# Microcontroller.net
KiCad netlist of a schematic drawn in Altium Designer
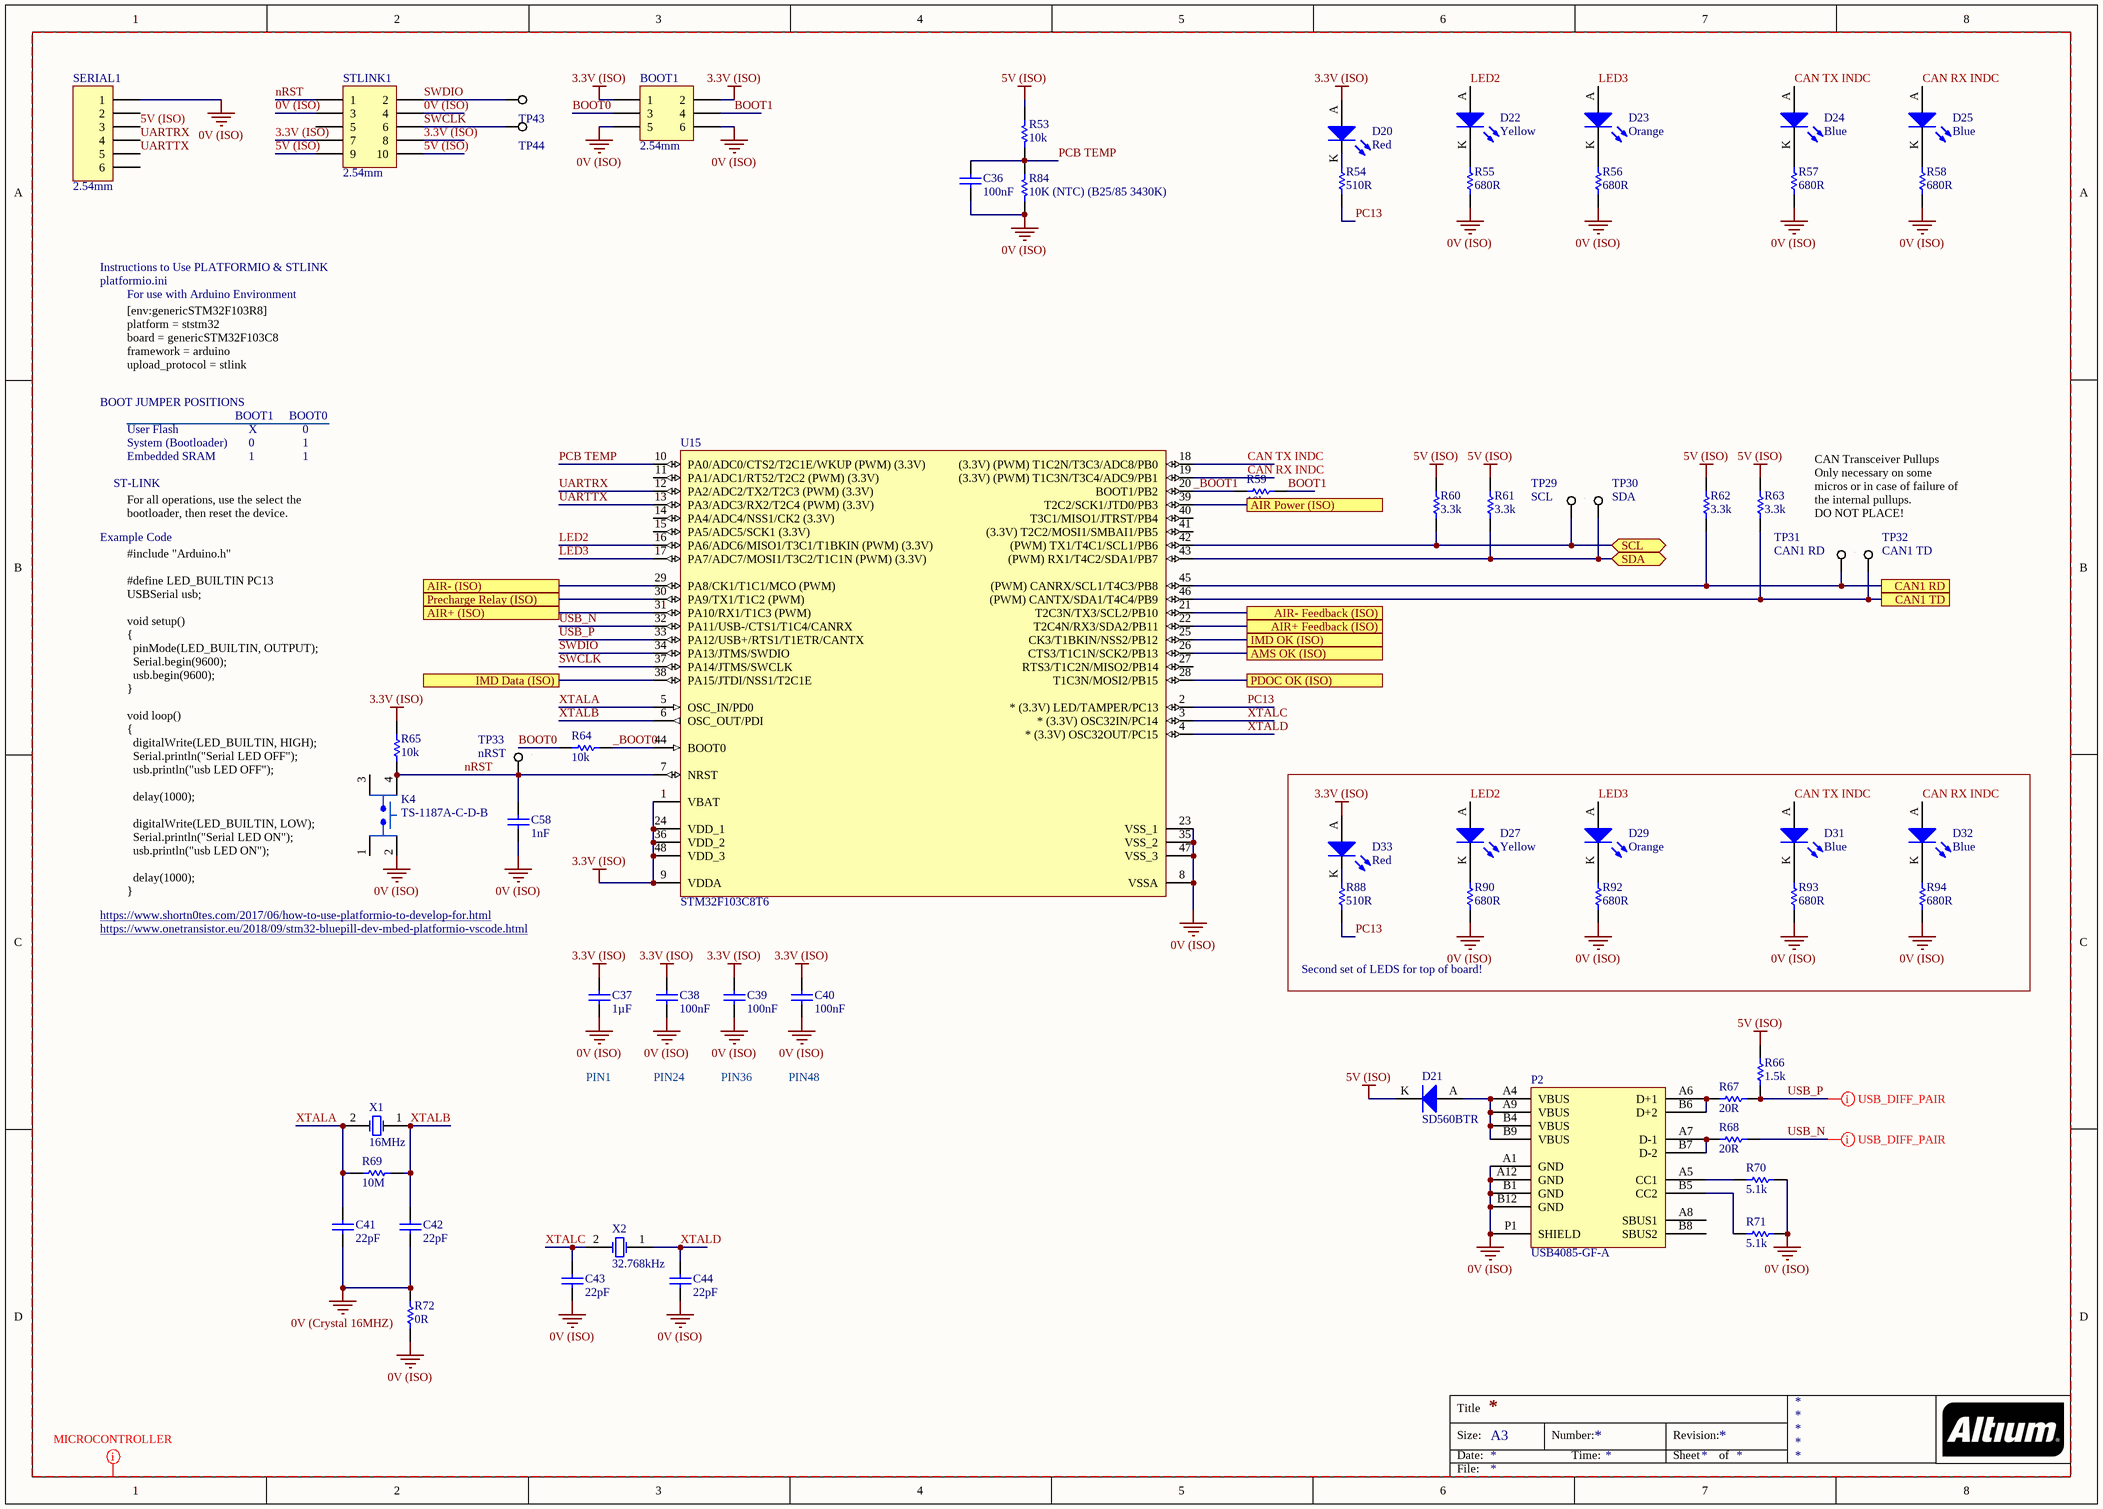
[diagram p0: Microcontroller.SchDoc]

(export (version "E")
  (design (tool "Eeschema 10.0.6"))
  (components
    (comp (ref "BOOT1")
      (value "2.54mm")
      (footprint "TH 2.54mm Header 2x3")
      (fields (field (name "PART NUMBER") "TH 2.54mm Header 2x3") (field (name "CONTACT") "NA"))
      (libsource (lib "ts_20-standard-connectors") (part "Header 2x3"))
    )
    (comp (ref "C36")
      (value "100nF")
      (footprint "0805")
      (fields
        (field (name "PART NUMBER") "GCM21BR71E104KA37L")
        (field (name "TOLERANCE") "10%")
        (field (name "MANUFACTURER") "muRata")
      )
      (libsource (lib "ts_20-standard-library") (part "Capacitor"))
    )
    (comp (ref "C37")
      (value "1µF")
      (footprint "0805")
      (fields
        (field (name "PART NUMBER") "GCM21BR71H105KA03L")
        (field (name "TOLERANCE") "±10%")
        (field (name "MANUFACTURER") "muRata")
      )
      (libsource (lib "ts_20-standard-library") (part "Capacitor"))
    )
    (comp (ref "C38")
      (value "100nF")
      (footprint "0805")
      (fields
        (field (name "PART NUMBER") "GCM21BR71H104KA37L")
        (field (name "TOLERANCE") "±10%")
        (field (name "MANUFACTURER") "muRata")
      )
      (libsource (lib "ts_20-standard-library") (part "Capacitor"))
    )
    (comp (ref "C39")
      (value "100nF")
      (footprint "0805")
      (fields
        (field (name "PART NUMBER") "GCM21BR71H104KA37L")
        (field (name "TOLERANCE") "±10%")
        (field (name "MANUFACTURER") "muRata")
      )
      (libsource (lib "ts_20-standard-library") (part "Capacitor"))
    )
    (comp (ref "C40")
      (value "100nF")
      (footprint "0805")
      (fields
        (field (name "PART NUMBER") "GCM21BR71H104KA37L")
        (field (name "TOLERANCE") "±10%")
        (field (name "MANUFACTURER") "muRata")
      )
      (libsource (lib "ts_20-standard-library") (part "Capacitor"))
    )
    (comp (ref "C41")
      (value "22pF")
      (footprint "0805")
      (fields
        (field (name "PART NUMBER") "GRM21A5C2E220JW01D")
        (field (name "TOLERANCE") "±5%")
        (field (name "MANUFACTURER") "muRata")
      )
      (libsource (lib "ts_20-standard-library") (part "Capacitor"))
    )
    (comp (ref "C42")
      (value "22pF")
      (footprint "0805")
      (fields
        (field (name "PART NUMBER") "GRM21A5C2E220JW01D")
        (field (name "TOLERANCE") "±5%")
        (field (name "MANUFACTURER") "muRata")
      )
      (libsource (lib "ts_20-standard-library") (part "Capacitor"))
    )
    (comp (ref "C43")
      (value "22pF")
      (footprint "0805")
      (fields
        (field (name "PART NUMBER") "GRM21A5C2E220JW01D")
        (field (name "TOLERANCE") "±5%")
        (field (name "MANUFACTURER") "muRata")
      )
      (libsource (lib "ts_20-standard-library") (part "Capacitor"))
    )
    (comp (ref "C44")
      (value "22pF")
      (footprint "0805")
      (fields
        (field (name "PART NUMBER") "GRM21A5C2E220JW01D")
        (field (name "TOLERANCE") "±5%")
        (field (name "MANUFACTURER") "muRata")
      )
      (libsource (lib "ts_20-standard-library") (part "Capacitor"))
    )
    (comp (ref "C58")
      (value "1nF")
      (footprint "0805")
      (fields
        (field (name "PART NUMBER") "GCM21BR71H102KA37L")
        (field (name "TOLERANCE") "10%")
        (field (name "MANUFACTURER") "muRata")
      )
      (libsource (lib "ts_20-standard-library") (part "Capacitor"))
    )
    (comp (ref "D20")
      (value "Red")
      (footprint "0805 LED")
      (description "Red LED Indication - Discrete 1.75V 0805 (2012 Metric)")
      (fields (field (name "MANUFACTURER") "ROHM Semiconductor") (field (name "PART NUMBER") "SML-210LTT86"))
      (libsource (lib "ts_20-standard-library") (part "LED"))
    )
    (comp (ref "D21")
      (value "SD560BTR")
      (footprint "SMB Diode")
      (description "1.2V_F 600V 5A SMB")
      (fields
        (field (name "MANUFACTURER") "SMC Diode Solutions")
        (field (name "DIGIKEY PART NUMBER") "1655-1530-2-ND")
      )
      (libsource (lib "ts_20-standard-library") (part "Diode"))
    )
    (comp (ref "D22")
      (value "Yellow")
      (footprint "0805 LED")
      (description "Yellow LED Indication - Discrete 1.75V 0805 (2012 Metric)")
      (fields (field (name "PART NUMBER") "SML-211YTT86") (field (name "MANUFACTURER") "ROHM Semiconductor"))
      (libsource (lib "ts_20-standard-library") (part "LED"))
    )
    (comp (ref "D23")
      (value "Orange")
      (footprint "0805 LED")
      (description "Orange LED Indication - Discrete 1.75V 0805 (2012 Metric)")
      (fields (field (name "PART NUMBER") "SML-211DTT86") (field (name "MANUFACTURER") "ROHM Semiconductor"))
      (libsource (lib "ts_20-standard-library") (part "LED"))
    )
    (comp (ref "D24")
      (value "Blue")
      (footprint "0805 LED")
      (description "LED BLUE CLEAR 2012 SMD")
      (fields
        (field (name "PART NUMBER") "SML-MN2BCTT86C")
        (field (name "MANUFACTURER") "ROHM Semiconductor")
      )
      (libsource (lib "ts_20-standard-library") (part "LED"))
    )
    (comp (ref "D25")
      (value "Blue")
      (footprint "0805 LED")
      (description "LED BLUE CLEAR 2012 SMD")
      (fields
        (field (name "PART NUMBER") "SML-MN2BCTT86C")
        (field (name "MANUFACTURER") "ROHM Semiconductor")
      )
      (libsource (lib "ts_20-standard-library") (part "LED"))
    )
    (comp (ref "D27")
      (value "Yellow")
      (footprint "0805 LED")
      (description "Yellow LED Indication - Discrete 1.75V 0805 (2012 Metric)")
      (fields (field (name "PART NUMBER") "SML-211YTT86") (field (name "MANUFACTURER") "ROHM Semiconductor"))
      (libsource (lib "ts_20-standard-library") (part "LED"))
    )
    (comp (ref "D29")
      (value "Orange")
      (footprint "0805 LED")
      (description "Orange LED Indication - Discrete 1.75V 0805 (2012 Metric)")
      (fields (field (name "PART NUMBER") "SML-211DTT86") (field (name "MANUFACTURER") "ROHM Semiconductor"))
      (libsource (lib "ts_20-standard-library") (part "LED"))
    )
    (comp (ref "D31")
      (value "Blue")
      (footprint "0805 LED")
      (description "LED BLUE CLEAR 2012 SMD")
      (fields
        (field (name "PART NUMBER") "SML-MN2BCTT86C")
        (field (name "MANUFACTURER") "ROHM Semiconductor")
      )
      (libsource (lib "ts_20-standard-library") (part "LED"))
    )
    (comp (ref "D32")
      (value "Blue")
      (footprint "0805 LED")
      (description "LED BLUE CLEAR 2012 SMD")
      (fields
        (field (name "PART NUMBER") "SML-MN2BCTT86C")
        (field (name "MANUFACTURER") "ROHM Semiconductor")
      )
      (libsource (lib "ts_20-standard-library") (part "LED"))
    )
    (comp (ref "D33")
      (value "Red")
      (footprint "0805 LED")
      (description "Red LED Indication - Discrete 1.75V 0805 (2012 Metric)")
      (fields (field (name "MANUFACTURER") "ROHM Semiconductor") (field (name "PART NUMBER") "SML-210LTT86"))
      (libsource (lib "ts_20-standard-library") (part "LED"))
    )
    (comp (ref "K4")
      (value "TS-1187A-C-D-B")
      (footprint "XKB SW-4.5")
      (description "TACTILE SWITCHES SPST 5.10MM X 5.10MM 0.80MM SMD ROHS")
      (fields (field (name "MANUFACTURER") "XKB Enerprise"))
      (libsource (lib "ts_20-standard-library") (part "SPST (Mom) Push Button"))
    )
    (comp (ref "P2")
      (value "USB4085-GF-A")
      (footprint "USB4085-GF-A")
      (description "USB - C (Type - C) USB 2.0 Receptacle Connector 16 Position Through Hole, Right Angle")
      (fields (field (name "DIGIKEY PART NUMBER") "2073-USB4085-GF-ACT-ND"))
      (libsource (lib "ts_20-standard-connectors") (part "USB4085-GF-A"))
    )
    (comp (ref "R53")
      (value "10k")
      (footprint "0805")
      (fields
        (field (name "PART NUMBER") "RC0805FR0710KL")
        (field (name "MANUFACTURER") "YAGEO")
        (field (name "TOLERANCE") "0.01")
      )
      (libsource (lib "ts_20-standard-library") (part "Resistor"))
    )
    (comp (ref "R54")
      (value "510R")
      (footprint "0805")
      (fields
        (field (name "MANUFACTURER") "YAGEO")
        (field (name "PART NUMBER") "RC0805FR07510RL")
        (field (name "TOLERANCE") "0.01")
      )
      (libsource (lib "ts_20-standard-library") (part "Resistor"))
    )
    (comp (ref "R55")
      (value "680R")
      (footprint "0805")
      (fields
        (field (name "PART NUMBER") "RC0805FR07680RL")
        (field (name "MANUFACTURER") "YAGEO")
        (field (name "TOLERANCE") "0.01")
      )
      (libsource (lib "ts_20-standard-library") (part "Resistor"))
    )
    (comp (ref "R56")
      (value "680R")
      (footprint "0805")
      (fields
        (field (name "PART NUMBER") "RC0805FR07680RL")
        (field (name "MANUFACTURER") "YAGEO")
        (field (name "TOLERANCE") "0.01")
      )
      (libsource (lib "ts_20-standard-library") (part "Resistor"))
    )
    (comp (ref "R57")
      (value "680R")
      (footprint "0805")
      (fields
        (field (name "PART NUMBER") "RC0805FR07680RL")
        (field (name "MANUFACTURER") "YAGEO")
        (field (name "TOLERANCE") "0.01")
      )
      (libsource (lib "ts_20-standard-library") (part "Resistor"))
    )
    (comp (ref "R58")
      (value "680R")
      (footprint "0805")
      (fields
        (field (name "PART NUMBER") "RC0805FR07680RL")
        (field (name "MANUFACTURER") "YAGEO")
        (field (name "TOLERANCE") "0.01")
      )
      (libsource (lib "ts_20-standard-library") (part "Resistor"))
    )
    (comp (ref "R59")
      (value "10k")
      (footprint "0805")
      (fields
        (field (name "PART NUMBER") "RC0805FR0710KL")
        (field (name "MANUFACTURER") "YAGEO")
        (field (name "TOLERANCE") "0.01")
      )
      (libsource (lib "ts_20-standard-library") (part "Resistor"))
    )
    (comp (ref "R60")
      (value "3.3k")
      (footprint "0805")
      (fields
        (field (name "PART NUMBER") "RC0805FR073K3L")
        (field (name "MANUFACTURER") "YAGEO")
        (field (name "TOLERANCE") "0.01")
      )
      (libsource (lib "ts_20-standard-library") (part "Resistor"))
    )
    (comp (ref "R61")
      (value "3.3k")
      (footprint "0805")
      (fields
        (field (name "PART NUMBER") "RC0805FR073K3L")
        (field (name "MANUFACTURER") "YAGEO")
        (field (name "TOLERANCE") "0.01")
      )
      (libsource (lib "ts_20-standard-library") (part "Resistor"))
    )
    (comp (ref "R62")
      (value "3.3k")
      (footprint "0805")
      (fields
        (field (name "PART NUMBER") "RC0805FR073K3L")
        (field (name "MANUFACTURER") "YAGEO")
        (field (name "TOLERANCE") "0.01")
      )
      (libsource (lib "ts_20-standard-library") (part "Resistor"))
    )
    (comp (ref "R63")
      (value "3.3k")
      (footprint "0805")
      (fields
        (field (name "PART NUMBER") "RC0805FR073K3L")
        (field (name "MANUFACTURER") "YAGEO")
        (field (name "TOLERANCE") "0.01")
      )
      (libsource (lib "ts_20-standard-library") (part "Resistor"))
    )
    (comp (ref "R64")
      (value "10k")
      (footprint "0805")
      (fields
        (field (name "PART NUMBER") "RC0805FR0710KL")
        (field (name "MANUFACTURER") "YAGEO")
        (field (name "TOLERANCE") "0.01")
      )
      (libsource (lib "ts_20-standard-library") (part "Resistor"))
    )
    (comp (ref "R65")
      (value "10k")
      (footprint "0805")
      (fields
        (field (name "MANUFACTURER") "YAGEO")
        (field (name "PART NUMBER") "RC0805FR0710KL")
        (field (name "TOLERANCE") "0.01")
      )
      (libsource (lib "ts_20-standard-library") (part "Resistor"))
    )
    (comp (ref "R66")
      (value "1.5k")
      (footprint "0805")
      (fields
        (field (name "PART NUMBER") "RC0805FR071K5L")
        (field (name "MANUFACTURER") "YAGEO")
        (field (name "TOLERANCE") "0.01")
      )
      (libsource (lib "ts_20-standard-library") (part "Resistor"))
    )
    (comp (ref "R67")
      (value "20R")
      (footprint "0805")
      (fields
        (field (name "PART NUMBER") "RC0805FR0720RL")
        (field (name "MANUFACTURER") "YAGEO")
        (field (name "TOLERANCE") "0.01")
      )
      (libsource (lib "ts_20-standard-library") (part "Resistor"))
    )
    (comp (ref "R68")
      (value "20R")
      (footprint "0805")
      (fields
        (field (name "PART NUMBER") "RC0805FR0720RL")
        (field (name "MANUFACTURER") "YAGEO")
        (field (name "TOLERANCE") "0.01")
      )
      (libsource (lib "ts_20-standard-library") (part "Resistor"))
    )
    (comp (ref "R69")
      (value "10M")
      (footprint "0805")
      (fields
        (field (name "PART NUMBER") "RC0805FR0710ML")
        (field (name "MANUFACTURER") "YAGEO")
        (field (name "TOLERANCE") "0.01")
      )
      (libsource (lib "ts_20-standard-library") (part "Resistor"))
    )
    (comp (ref "R70")
      (value "5.1k")
      (footprint "0805")
      (fields
        (field (name "PART NUMBER") "RC0805FR075K1L")
        (field (name "MANUFACTURER") "YAGEO")
        (field (name "TOLERANCE") "0.01")
      )
      (libsource (lib "ts_20-standard-library") (part "Resistor"))
    )
    (comp (ref "R71")
      (value "5.1k")
      (footprint "0805")
      (fields
        (field (name "PART NUMBER") "RC0805FR075K1L")
        (field (name "MANUFACTURER") "YAGEO")
        (field (name "TOLERANCE") "0.01")
      )
      (libsource (lib "ts_20-standard-library") (part "Resistor"))
    )
    (comp (ref "R72")
      (value "0R")
      (footprint "0805")
      (fields
        (field (name "PART NUMBER") "RC0805FR070RL")
        (field (name "MANUFACTURER") "YAGEO")
        (field (name "TOLERANCE") "0.01")
      )
      (libsource (lib "ts_20-standard-library") (part "Resistor"))
    )
    (comp (ref "R84")
      (value "10K (NTC) (B25/85 3430K)")
      (footprint "0805")
      (fields
        (field (name "PART NUMBER") "NTCS0805E3103FLT")
        (field (name "MANUFACTURER") "Vishay Beyschlag")
        (field (name "TOLERANCE") "0.01")
      )
      (libsource (lib "ts_20-standard-library") (part "Resistor"))
    )
    (comp (ref "R88")
      (value "510R")
      (footprint "0805")
      (fields
        (field (name "MANUFACTURER") "YAGEO")
        (field (name "PART NUMBER") "RC0805FR07510RL")
        (field (name "TOLERANCE") "0.01")
      )
      (libsource (lib "ts_20-standard-library") (part "Resistor"))
    )
    (comp (ref "R90")
      (value "680R")
      (footprint "0805")
      (fields
        (field (name "PART NUMBER") "RC0805FR07680RL")
        (field (name "MANUFACTURER") "YAGEO")
        (field (name "TOLERANCE") "0.01")
      )
      (libsource (lib "ts_20-standard-library") (part "Resistor"))
    )
    (comp (ref "R92")
      (value "680R")
      (footprint "0805")
      (fields
        (field (name "PART NUMBER") "RC0805FR07680RL")
        (field (name "MANUFACTURER") "YAGEO")
        (field (name "TOLERANCE") "0.01")
      )
      (libsource (lib "ts_20-standard-library") (part "Resistor"))
    )
    (comp (ref "R93")
      (value "680R")
      (footprint "0805")
      (fields
        (field (name "PART NUMBER") "RC0805FR07680RL")
        (field (name "MANUFACTURER") "YAGEO")
        (field (name "TOLERANCE") "0.01")
      )
      (libsource (lib "ts_20-standard-library") (part "Resistor"))
    )
    (comp (ref "R94")
      (value "680R")
      (footprint "0805")
      (fields
        (field (name "PART NUMBER") "RC0805FR07680RL")
        (field (name "MANUFACTURER") "YAGEO")
        (field (name "TOLERANCE") "0.01")
      )
      (libsource (lib "ts_20-standard-library") (part "Resistor"))
    )
    (comp (ref "SERIAL1")
      (value "2.54mm")
      (footprint "TH 2.54mm Header 1x6")
      (fields (field (name "PART NUMBER") "TH 2.54mm Header 1x6") (field (name "CONTACT") "NA"))
      (libsource (lib "ts_20-standard-connectors") (part "Header 1x6"))
    )
    (comp (ref "STLINK1")
      (value "2.54mm")
      (footprint "TH 2.54mm Header 2x5")
      (fields (field (name "PART NUMBER") "TH 2.54mm Header 2x5") (field (name "CONTACT") "NA"))
      (libsource (lib "ts_20-standard-connectors") (part "Header 2x5"))
    )
    (comp (ref "TP29")
      (value "SCL")
      (footprint "SMD Test Point 1mm")
      (fields (field (name "PART NUMBER") "SMD Test Point Small") (field (name "CONTACT") "NA"))
      (libsource (lib "ts_20-standard-connectors") (part "Test Point Small"))
    )
    (comp (ref "TP30")
      (value "SDA")
      (footprint "SMD Test Point 1mm")
      (fields (field (name "PART NUMBER") "SMD Test Point Small") (field (name "CONTACT") "NA"))
      (libsource (lib "ts_20-standard-connectors") (part "Test Point Small"))
    )
    (comp (ref "TP31")
      (value "CAN1 RD")
      (footprint "SMD Test Point 1mm")
      (fields (field (name "PART NUMBER") "SMD Test Point Small") (field (name "CONTACT") "NA"))
      (libsource (lib "ts_20-standard-connectors") (part "Test Point Small"))
    )
    (comp (ref "TP32")
      (value "CAN1 TD")
      (footprint "SMD Test Point 1mm")
      (fields (field (name "PART NUMBER") "SMD Test Point Small") (field (name "CONTACT") "NA"))
      (libsource (lib "ts_20-standard-connectors") (part "Test Point Small"))
    )
    (comp (ref "TP33")
      (value "nRST")
      (footprint "SMD Test Point 1mm")
      (fields (field (name "PART NUMBER") "SMD Test Point Small") (field (name "CONTACT") "NA"))
      (libsource (lib "ts_20-standard-connectors") (part "Test Point Small"))
    )
    (comp (ref "TP43")
      (value "0mm")
      (footprint "SMD Test Point 1mm")
      (fields (field (name "PART NUMBER") "SMD Test Point Small") (field (name "CONTACT") "NA"))
      (libsource (lib "ts_20-standard-connectors") (part "Test Point Small"))
    )
    (comp (ref "TP44")
      (value "0mm")
      (footprint "SMD Test Point 1mm")
      (fields (field (name "PART NUMBER") "SMD Test Point Small") (field (name "CONTACT") "NA"))
      (libsource (lib "ts_20-standard-connectors") (part "Test Point Small"))
    )
    (comp (ref "U15")
      (value "STM32F103C8T6")
      (footprint "STM 48-LQFP")
      (description "ARM® Cortex®-M3 STM32F1 Microcontroller IC 32-Bit 72MHz 64KB (64K x 8) FLASH")
      (fields
        (field (name "MANUFACTURER") "STMicroelectronics")
        (field (name "DIGIKEY PART NUMBER") "497-6063-ND")
      )
      (libsource (lib "ts_20-standard-library") (part "STM32F103C8T6"))
    )
    (comp (ref "X1")
      (value "16MHz")
      (footprint "Abracon HC-49/US")
      (fields
        (field (name "PART NUMBER") "ABLS-16.000MHZ-B4-T")
        (field (name "MANUFACTURER") "Abracon LLC")
        (field (name "DIGIKEY PART NUMBER") "535-10226-1-ND")
      )
      (libsource (lib "ts_20-standard-library") (part "Crystal"))
    )
    (comp (ref "X2")
      (value "32.768kHz")
      (footprint "EPSON 2-SMD")
      (fields
        (field (name "PART NUMBER") "FC-135 32.7680KA-A5")
        (field (name "MANUFACTURER") "EPSON")
        (field (name "DIGIKEY PART NUMBER") "SER4103TR-ND")
      )
      (libsource (lib "ts_20-standard-library") (part "Crystal"))
    )
  )
  (nets
    (net (code "1") (name "/AIR Power (ISO)") (class "Default")
      (node (ref "U15") (pin "39") (pinfunction "T2C2/SCK1/JTD0/PB3_39") (pintype "bidirectional"))
    )
    (net (code "2") (name "/AIR+ (ISO)") (class "Default")
      (node (ref "U15") (pin "31") (pinfunction "PA10/RX1/T1C3_(PWM)_31") (pintype "bidirectional"))
    )
    (net (code "3") (name "/AIR+ Feedback (ISO)") (class "Default")
      (node (ref "U15") (pin "22") (pinfunction "T2C4N/RX3/SDA2/PB11_22") (pintype "bidirectional"))
    )
    (net (code "4") (name "/AIR- (ISO)") (class "Default")
      (node (ref "U15") (pin "29") (pinfunction "PA8/CK1/T1C1/MCO_(PWM)_29") (pintype "bidirectional"))
    )
    (net (code "5") (name "/AIR- Feedback (ISO)") (class "Default")
      (node (ref "U15") (pin "21") (pinfunction "T2C3N/TX3/SCL2/PB10_21") (pintype "bidirectional"))
    )
    (net (code "6") (name "/AMS OK (ISO)") (class "Default")
      (node (ref "U15") (pin "26") (pinfunction "CTS3/T1C1N/SCK2/PB13_26") (pintype "bidirectional"))
    )
    (net (code "7") (name "/BOOT0") (class "Default")
      (node (ref "BOOT1") (pin "3") (pinfunction "3_3") (pintype "passive"))
      (node (ref "R64") (pin "1") (pinfunction "1_1") (pintype "passive"))
    )
    (net (code "8") (name "/BOOT1") (class "Default")
      (node (ref "BOOT1") (pin "4") (pinfunction "4_4") (pintype "passive"))
      (node (ref "R59") (pin "2") (pinfunction "2_2") (pintype "passive"))
    )
    (net (code "9") (name "/CAN RX INDC") (class "Default")
      (node (ref "D25") (pin "A") (pinfunction "A_A") (pintype "passive"))
      (node (ref "D32") (pin "A") (pinfunction "A_A") (pintype "passive"))
      (node (ref "U15") (pin "19") (pinfunction "(3.3V)_(PWM)_T1C3N/T3C4/ADC9/PB1_19") (pintype "bidirectional"))
    )
    (net (code "10") (name "/CAN TX INDC") (class "Default")
      (node (ref "D24") (pin "A") (pinfunction "A_A") (pintype "passive"))
      (node (ref "D31") (pin "A") (pinfunction "A_A") (pintype "passive"))
      (node (ref "U15") (pin "18") (pinfunction "(3.3V)_(PWM)_T1C2N/T3C3/ADC8/PB0_18") (pintype "bidirectional"))
    )
    (net (code "11") (name "/CAN1 RD") (class "Default")
      (node (ref "R62") (pin "1") (pinfunction "1_1") (pintype "passive"))
      (node (ref "TP31") (pin "1") (pinfunction "1_1") (pintype "passive"))
      (node (ref "U15") (pin "45") (pinfunction "(PWM)_CANRX/SCL1/T4C3/PB8_45") (pintype "bidirectional"))
    )
    (net (code "12") (name "/CAN1 TD") (class "Default")
      (node (ref "R63") (pin "1") (pinfunction "1_1") (pintype "passive"))
      (node (ref "TP32") (pin "1") (pinfunction "1_1") (pintype "passive"))
      (node (ref "U15") (pin "46") (pinfunction "(PWM)_CANTX/SDA1/T4C4/PB9_46") (pintype "bidirectional"))
    )
    (net (code "13") (name "/IMD Data (ISO)") (class "Default")
      (node (ref "U15") (pin "38") (pinfunction "PA15/JTDI/NSS1/T2C1E_38") (pintype "bidirectional"))
    )
    (net (code "14") (name "/IMD OK (ISO)") (class "Default")
      (node (ref "U15") (pin "25") (pinfunction "CK3/T1BKIN/NSS2/PB12_25") (pintype "bidirectional"))
    )
    (net (code "15") (name "/LED2") (class "Default")
      (node (ref "D22") (pin "A") (pinfunction "A_A") (pintype "passive"))
      (node (ref "D27") (pin "A") (pinfunction "A_A") (pintype "passive"))
      (node (ref "U15") (pin "16") (pinfunction "PA6/ADC6/MISO1/T3C1/T1BKIN_(PWM)_(3.3V)_16") (pintype "bidirectional"))
    )
    (net (code "16") (name "/LED3") (class "Default")
      (node (ref "D23") (pin "A") (pinfunction "A_A") (pintype "passive"))
      (node (ref "D29") (pin "A") (pinfunction "A_A") (pintype "passive"))
      (node (ref "U15") (pin "17") (pinfunction "PA7/ADC7/MOSI1/T3C2/T1C1N_(PWM)_(3.3V)_17") (pintype "bidirectional"))
    )
    (net (code "17") (name "/PC13") (class "Default")
      (node (ref "R54") (pin "1") (pinfunction "1_1") (pintype "passive"))
      (node (ref "R88") (pin "1") (pinfunction "1_1") (pintype "passive"))
      (node (ref "U15") (pin "2") (pinfunction "*_(3.3V)_LED/TAMPER/PC13_2") (pintype "bidirectional"))
    )
    (net (code "18") (name "/PCB TEMP") (class "Default")
      (node (ref "C36") (pin "2") (pinfunction "2_2") (pintype "passive"))
      (node (ref "R53") (pin "1") (pinfunction "1_1") (pintype "passive"))
      (node (ref "R84") (pin "2") (pinfunction "2_2") (pintype "passive"))
      (node (ref "U15") (pin "10") (pinfunction "PA0/ADC0/CTS2/T2C1E/WKUP_(PWM)_(3.3V)_10") (pintype "bidirectional"))
    )
    (net (code "19") (name "/PDOC OK (ISO)") (class "Default")
      (node (ref "U15") (pin "28") (pinfunction "T1C3N/MOSI2/PB15_28") (pintype "bidirectional"))
    )
    (net (code "20") (name "/Precharge Relay (ISO)") (class "Default")
      (node (ref "U15") (pin "30") (pinfunction "PA9/TX1/T1C2_(PWM)_30") (pintype "bidirectional"))
    )
    (net (code "21") (name "/SCL") (class "Default")
      (node (ref "R60") (pin "1") (pinfunction "1_1") (pintype "passive"))
      (node (ref "TP29") (pin "1") (pinfunction "1_1") (pintype "passive"))
      (node (ref "U15") (pin "42") (pinfunction "(PWM)_TX1/T4C1/SCL1/PB6_42") (pintype "bidirectional"))
    )
    (net (code "22") (name "/SDA") (class "Default")
      (node (ref "R61") (pin "1") (pinfunction "1_1") (pintype "passive"))
      (node (ref "TP30") (pin "1") (pinfunction "1_1") (pintype "passive"))
      (node (ref "U15") (pin "43") (pinfunction "(PWM)_RX1/T4C2/SDA1/PB7_43") (pintype "bidirectional"))
    )
    (net (code "23") (name "/SWCLK") (class "Default")
      (node (ref "STLINK1") (pin "6") (pinfunction "6_6") (pintype "passive"))
      (node (ref "TP44") (pin "1") (pinfunction "1_1") (pintype "passive"))
      (node (ref "U15") (pin "37") (pinfunction "PA14/JTMS/SWCLK_37") (pintype "bidirectional"))
    )
    (net (code "24") (name "/SWDIO") (class "Default")
      (node (ref "STLINK1") (pin "2") (pinfunction "2_2") (pintype "passive"))
      (node (ref "TP43") (pin "1") (pinfunction "1_1") (pintype "passive"))
      (node (ref "U15") (pin "34") (pinfunction "PA13/JTMS/SWDIO_34") (pintype "bidirectional"))
    )
    (net (code "25") (name "/UARTRX") (class "Default")
      (node (ref "SERIAL1") (pin "4") (pinfunction "4_4") (pintype "passive"))
      (node (ref "U15") (pin "12") (pinfunction "PA2/ADC2/TX2/T2C3_(PWM)_(3.3V)_12") (pintype "bidirectional"))
    )
    (net (code "26") (name "/UARTTX") (class "Default")
      (node (ref "SERIAL1") (pin "5") (pinfunction "5_5") (pintype "passive"))
      (node (ref "U15") (pin "13") (pinfunction "PA3/ADC3/RX2/T2C4_(PWM)_(3.3V)_13") (pintype "bidirectional"))
    )
    (net (code "27") (name "/USB_N") (class "Default")
      (node (ref "R68") (pin "2") (pinfunction "2_2") (pintype "passive"))
      (node (ref "U15") (pin "32") (pinfunction "PA11/USB-/CTS1/T1C4/CANRX_32") (pintype "bidirectional"))
    )
    (net (code "28") (name "/USB_P") (class "Default")
      (node (ref "R66") (pin "1") (pinfunction "1_1") (pintype "passive"))
      (node (ref "R67") (pin "2") (pinfunction "2_2") (pintype "passive"))
      (node (ref "U15") (pin "33") (pinfunction "PA12/USB+/RTS1/T1ETR/CANTX_33") (pintype "bidirectional"))
    )
    (net (code "29") (name "/XTALA") (class "Default")
      (node (ref "C41") (pin "2") (pinfunction "2_2") (pintype "passive"))
      (node (ref "R69") (pin "2") (pinfunction "2_2") (pintype "passive"))
      (node (ref "U15") (pin "5") (pinfunction "OSC_IN/PD0_5") (pintype "input"))
      (node (ref "X1") (pin "2") (pinfunction "OSC2_2") (pintype "passive"))
    )
    (net (code "30") (name "/XTALB") (class "Default")
      (node (ref "C42") (pin "2") (pinfunction "2_2") (pintype "passive"))
      (node (ref "R69") (pin "1") (pinfunction "1_1") (pintype "passive"))
      (node (ref "U15") (pin "6") (pinfunction "OSC_OUT/PDI_6") (pintype "output"))
      (node (ref "X1") (pin "1") (pinfunction "OSC1_1") (pintype "passive"))
    )
    (net (code "31") (name "/XTALC") (class "Default")
      (node (ref "C43") (pin "2") (pinfunction "2_2") (pintype "passive"))
      (node (ref "U15") (pin "3") (pinfunction "*_(3.3V)_OSC32IN/PC14_3") (pintype "bidirectional"))
      (node (ref "X2") (pin "2") (pinfunction "OSC2_2") (pintype "passive"))
    )
    (net (code "32") (name "/XTALD") (class "Default")
      (node (ref "C44") (pin "2") (pinfunction "2_2") (pintype "passive"))
      (node (ref "U15") (pin "4") (pinfunction "*_(3.3V)_OSC32OUT/PC15_4") (pintype "bidirectional"))
      (node (ref "X2") (pin "1") (pinfunction "OSC1_1") (pintype "passive"))
    )
    (net (code "33") (name "/_BOOT0") (class "Default")
      (node (ref "R64") (pin "2") (pinfunction "2_2") (pintype "passive"))
      (node (ref "U15") (pin "44") (pinfunction "BOOT0_44") (pintype "input"))
    )
    (net (code "34") (name "/_BOOT1") (class "Default")
      (node (ref "R59") (pin "1") (pinfunction "1_1") (pintype "passive"))
      (node (ref "U15") (pin "20") (pinfunction "BOOT1/PB2_20") (pintype "bidirectional"))
    )
    (net (code "35") (name "/nRST") (class "Default")
      (node (ref "C58") (pin "2") (pinfunction "2_2") (pintype "passive"))
      (node (ref "K4") (pin "4") (pinfunction "VDD_4") (pintype "passive"))
      (node (ref "R65") (pin "1") (pinfunction "1_1") (pintype "passive"))
      (node (ref "STLINK1") (pin "1") (pinfunction "1_1") (pintype "passive"))
      (node (ref "TP33") (pin "1") (pinfunction "1_1") (pintype "passive"))
      (node (ref "U15") (pin "7") (pinfunction "NRST_7") (pintype "bidirectional"))
    )
    (net (code "36") (name "0V (Crystal 16MHZ)") (class "Default")
      (node (ref "C41") (pin "1") (pinfunction "1_1") (pintype "passive"))
      (node (ref "C42") (pin "1") (pinfunction "1_1") (pintype "passive"))
      (node (ref "R72") (pin "2") (pinfunction "2_2") (pintype "passive"))
    )
    (net (code "37") (name "0V (ISO)") (class "Default")
      (node (ref "BOOT1") (pin "5") (pinfunction "5_5") (pintype "passive"))
      (node (ref "BOOT1") (pin "6") (pinfunction "6_6") (pintype "passive"))
      (node (ref "C36") (pin "1") (pinfunction "1_1") (pintype "passive"))
      (node (ref "C37") (pin "1") (pinfunction "1_1") (pintype "passive"))
      (node (ref "C38") (pin "1") (pinfunction "1_1") (pintype "passive"))
      (node (ref "C39") (pin "1") (pinfunction "1_1") (pintype "passive"))
      (node (ref "C40") (pin "1") (pinfunction "1_1") (pintype "passive"))
      (node (ref "C43") (pin "1") (pinfunction "1_1") (pintype "passive"))
      (node (ref "C44") (pin "1") (pinfunction "1_1") (pintype "passive"))
      (node (ref "C58") (pin "1") (pinfunction "1_1") (pintype "passive"))
      (node (ref "K4") (pin "2") (pinfunction "VDD_2") (pintype "passive"))
      (node (ref "P2") (pin "A1") (pinfunction "GND_A1") (pintype "passive"))
      (node (ref "P2") (pin "A12") (pinfunction "GND_A12") (pintype "passive"))
      (node (ref "P2") (pin "B1") (pinfunction "GND_B1") (pintype "passive"))
      (node (ref "P2") (pin "B12") (pinfunction "GND_B12") (pintype "passive"))
      (node (ref "P2") (pin "P1") (pinfunction "SHIELD_P1") (pintype "passive"))
      (node (ref "R55") (pin "1") (pinfunction "1_1") (pintype "passive"))
      (node (ref "R56") (pin "1") (pinfunction "1_1") (pintype "passive"))
      (node (ref "R57") (pin "1") (pinfunction "1_1") (pintype "passive"))
      (node (ref "R58") (pin "1") (pinfunction "1_1") (pintype "passive"))
      (node (ref "R70") (pin "2") (pinfunction "2_2") (pintype "passive"))
      (node (ref "R71") (pin "2") (pinfunction "2_2") (pintype "passive"))
      (node (ref "R72") (pin "1") (pinfunction "1_1") (pintype "passive"))
      (node (ref "R84") (pin "1") (pinfunction "1_1") (pintype "passive"))
      (node (ref "R90") (pin "1") (pinfunction "1_1") (pintype "passive"))
      (node (ref "R92") (pin "1") (pinfunction "1_1") (pintype "passive"))
      (node (ref "R93") (pin "1") (pinfunction "1_1") (pintype "passive"))
      (node (ref "R94") (pin "1") (pinfunction "1_1") (pintype "passive"))
      (node (ref "SERIAL1") (pin "1") (pinfunction "1_1") (pintype "passive"))
      (node (ref "STLINK1") (pin "3") (pinfunction "3_3") (pintype "passive"))
      (node (ref "STLINK1") (pin "4") (pinfunction "4_4") (pintype "passive"))
      (node (ref "U15") (pin "23") (pinfunction "VSS_1_23") (pintype "power_in"))
      (node (ref "U15") (pin "35") (pinfunction "VSS_2_35") (pintype "power_in"))
      (node (ref "U15") (pin "47") (pinfunction "VSS_3_47") (pintype "power_in"))
      (node (ref "U15") (pin "8") (pinfunction "VSSA_8") (pintype "power_in"))
    )
    (net (code "38") (name "3.3V (ISO)") (class "Default")
      (node (ref "BOOT1") (pin "1") (pinfunction "1_1") (pintype "passive"))
      (node (ref "BOOT1") (pin "2") (pinfunction "2_2") (pintype "passive"))
      (node (ref "C37") (pin "2") (pinfunction "2_2") (pintype "passive"))
      (node (ref "C38") (pin "2") (pinfunction "2_2") (pintype "passive"))
      (node (ref "C39") (pin "2") (pinfunction "2_2") (pintype "passive"))
      (node (ref "C40") (pin "2") (pinfunction "2_2") (pintype "passive"))
      (node (ref "D20") (pin "A") (pinfunction "A_A") (pintype "passive"))
      (node (ref "D33") (pin "A") (pinfunction "A_A") (pintype "passive"))
      (node (ref "R65") (pin "2") (pinfunction "2_2") (pintype "passive"))
      (node (ref "STLINK1") (pin "7") (pinfunction "7_7") (pintype "passive"))
      (node (ref "STLINK1") (pin "8") (pinfunction "8_8") (pintype "passive"))
      (node (ref "U15") (pin "1") (pinfunction "VBAT_1") (pintype "power_in"))
      (node (ref "U15") (pin "24") (pinfunction "VDD_1_24") (pintype "power_in"))
      (node (ref "U15") (pin "36") (pinfunction "VDD_2_36") (pintype "power_in"))
      (node (ref "U15") (pin "48") (pinfunction "VDD_3_48") (pintype "power_in"))
      (node (ref "U15") (pin "9") (pinfunction "VDDA_9") (pintype "power_in"))
    )
    (net (code "39") (name "5V (ISO)") (class "Default")
      (node (ref "D21") (pin "K") (pinfunction "K_K") (pintype "passive"))
      (node (ref "R53") (pin "2") (pinfunction "2_2") (pintype "passive"))
      (node (ref "R60") (pin "2") (pinfunction "2_2") (pintype "passive"))
      (node (ref "R61") (pin "2") (pinfunction "2_2") (pintype "passive"))
      (node (ref "R62") (pin "2") (pinfunction "2_2") (pintype "passive"))
      (node (ref "R63") (pin "2") (pinfunction "2_2") (pintype "passive"))
      (node (ref "R66") (pin "2") (pinfunction "2_2") (pintype "passive"))
      (node (ref "SERIAL1") (pin "3") (pinfunction "3_3") (pintype "passive"))
      (node (ref "STLINK1") (pin "10") (pinfunction "10_10") (pintype "passive"))
      (node (ref "STLINK1") (pin "9") (pinfunction "9_9") (pintype "passive"))
    )
    (net (code "40") (name "Net-(D20-PadK)") (class "Default")
      (node (ref "D20") (pin "K") (pinfunction "K_K") (pintype "passive"))
      (node (ref "R54") (pin "2") (pinfunction "2_2") (pintype "passive"))
    )
    (net (code "41") (name "Net-(D21-PadA)") (class "Default")
      (node (ref "D21") (pin "A") (pinfunction "A_A") (pintype "passive"))
      (node (ref "P2") (pin "A4") (pinfunction "VBUS_A4") (pintype "passive"))
      (node (ref "P2") (pin "A9") (pinfunction "VBUS_A9") (pintype "passive"))
      (node (ref "P2") (pin "B4") (pinfunction "VBUS_B4") (pintype "passive"))
      (node (ref "P2") (pin "B9") (pinfunction "VBUS_B9") (pintype "passive"))
    )
    (net (code "42") (name "Net-(D22-PadK)") (class "Default")
      (node (ref "D22") (pin "K") (pinfunction "K_K") (pintype "passive"))
      (node (ref "R55") (pin "2") (pinfunction "2_2") (pintype "passive"))
    )
    (net (code "43") (name "Net-(D23-PadK)") (class "Default")
      (node (ref "D23") (pin "K") (pinfunction "K_K") (pintype "passive"))
      (node (ref "R56") (pin "2") (pinfunction "2_2") (pintype "passive"))
    )
    (net (code "44") (name "Net-(D24-PadK)") (class "Default")
      (node (ref "D24") (pin "K") (pinfunction "K_K") (pintype "passive"))
      (node (ref "R57") (pin "2") (pinfunction "2_2") (pintype "passive"))
    )
    (net (code "45") (name "Net-(D25-PadK)") (class "Default")
      (node (ref "D25") (pin "K") (pinfunction "K_K") (pintype "passive"))
      (node (ref "R58") (pin "2") (pinfunction "2_2") (pintype "passive"))
    )
    (net (code "46") (name "Net-(D27-PadK)") (class "Default")
      (node (ref "D27") (pin "K") (pinfunction "K_K") (pintype "passive"))
      (node (ref "R90") (pin "2") (pinfunction "2_2") (pintype "passive"))
    )
    (net (code "47") (name "Net-(D29-PadK)") (class "Default")
      (node (ref "D29") (pin "K") (pinfunction "K_K") (pintype "passive"))
      (node (ref "R92") (pin "2") (pinfunction "2_2") (pintype "passive"))
    )
    (net (code "48") (name "Net-(D31-PadK)") (class "Default")
      (node (ref "D31") (pin "K") (pinfunction "K_K") (pintype "passive"))
      (node (ref "R93") (pin "2") (pinfunction "2_2") (pintype "passive"))
    )
    (net (code "49") (name "Net-(D32-PadK)") (class "Default")
      (node (ref "D32") (pin "K") (pinfunction "K_K") (pintype "passive"))
      (node (ref "R94") (pin "2") (pinfunction "2_2") (pintype "passive"))
    )
    (net (code "50") (name "Net-(D33-PadK)") (class "Default")
      (node (ref "D33") (pin "K") (pinfunction "K_K") (pintype "passive"))
      (node (ref "R88") (pin "2") (pinfunction "2_2") (pintype "passive"))
    )
    (net (code "51") (name "Net-(P2-CC1)") (class "Default")
      (node (ref "P2") (pin "A5") (pinfunction "CC1_A5") (pintype "passive"))
      (node (ref "R70") (pin "1") (pinfunction "1_1") (pintype "passive"))
    )
    (net (code "52") (name "Net-(P2-CC2)") (class "Default")
      (node (ref "P2") (pin "B5") (pinfunction "CC2_B5") (pintype "passive"))
      (node (ref "R71") (pin "1") (pinfunction "1_1") (pintype "passive"))
    )
    (net (code "53") (name "Net-(P2-D+1)") (class "Default")
      (node (ref "P2") (pin "A6") (pinfunction "D+1_A6") (pintype "passive"))
      (node (ref "P2") (pin "B6") (pinfunction "D+2_B6") (pintype "passive"))
      (node (ref "R67") (pin "1") (pinfunction "1_1") (pintype "passive"))
    )
    (net (code "54") (name "Net-(P2-D-1)") (class "Default")
      (node (ref "P2") (pin "A7") (pinfunction "D-1_A7") (pintype "passive"))
      (node (ref "P2") (pin "B7") (pinfunction "D-2_B7") (pintype "passive"))
      (node (ref "R68") (pin "1") (pinfunction "1_1") (pintype "passive"))
    )
    (net (code "55") (name "unconnected-(K4-VDD-Pad1)") (class "Default")
      (node (ref "K4") (pin "1") (pinfunction "VDD_1") (pintype "passive"))
    )
    (net (code "56") (name "unconnected-(K4-VDD-Pad3)") (class "Default")
      (node (ref "K4") (pin "3") (pinfunction "VDD_3") (pintype "passive"))
    )
    (net (code "57") (name "unconnected-(P2-SBUS1-PadA8)") (class "Default")
      (node (ref "P2") (pin "A8") (pinfunction "SBUS1_A8") (pintype "passive"))
    )
    (net (code "58") (name "unconnected-(P2-SBUS2-PadB8)") (class "Default")
      (node (ref "P2") (pin "B8") (pinfunction "SBUS2_B8") (pintype "passive"))
    )
    (net (code "59") (name "unconnected-(SERIAL1-Pad2)") (class "Default")
      (node (ref "SERIAL1") (pin "2") (pinfunction "2_2") (pintype "passive"))
    )
    (net (code "60") (name "unconnected-(SERIAL1-Pad6)") (class "Default")
      (node (ref "SERIAL1") (pin "6") (pinfunction "6_6") (pintype "passive"))
    )
    (net (code "61") (name "unconnected-(STLINK1-Pad5)") (class "Default")
      (node (ref "STLINK1") (pin "5") (pinfunction "5_5") (pintype "passive"))
    )
    (net (code "62") (name "unconnected-(U15-(3.3V)_T2C2{slash}MOSI1{slash}SMBAI1{slash}PB5-Pad41)") (class "Default")
      (node (ref "U15") (pin "41") (pinfunction "(3.3V)_T2C2/MOSI1/SMBAI1/PB5_41") (pintype "bidirectional"))
    )
    (net (code "63") (name "unconnected-(U15-PA1{slash}ADC1{slash}RT52{slash}T2C2_(PWM)_(3.3V)-Pad11)") (class "Default")
      (node (ref "U15") (pin "11") (pinfunction "PA1/ADC1/RT52/T2C2_(PWM)_(3.3V)_11") (pintype "bidirectional"))
    )
    (net (code "64") (name "unconnected-(U15-PA4{slash}ADC4{slash}NSS1{slash}CK2_(3.3V)-Pad14)") (class "Default")
      (node (ref "U15") (pin "14") (pinfunction "PA4/ADC4/NSS1/CK2_(3.3V)_14") (pintype "bidirectional"))
    )
    (net (code "65") (name "unconnected-(U15-PA5{slash}ADC5{slash}SCK1_(3.3V)-Pad15)") (class "Default")
      (node (ref "U15") (pin "15") (pinfunction "PA5/ADC5/SCK1_(3.3V)_15") (pintype "bidirectional"))
    )
    (net (code "66") (name "unconnected-(U15-RTS3{slash}T1C2N{slash}MISO2{slash}PB14-Pad27)") (class "Default")
      (node (ref "U15") (pin "27") (pinfunction "RTS3/T1C2N/MISO2/PB14_27") (pintype "bidirectional"))
    )
    (net (code "67") (name "unconnected-(U15-T3C1{slash}MISO1{slash}JTRST{slash}PB4-Pad40)") (class "Default")
      (node (ref "U15") (pin "40") (pinfunction "T3C1/MISO1/JTRST/PB4_40") (pintype "bidirectional"))
    )
  )
)
